# DSI_LCD.net
KiCad netlist of a schematic drawn in Altium Designer
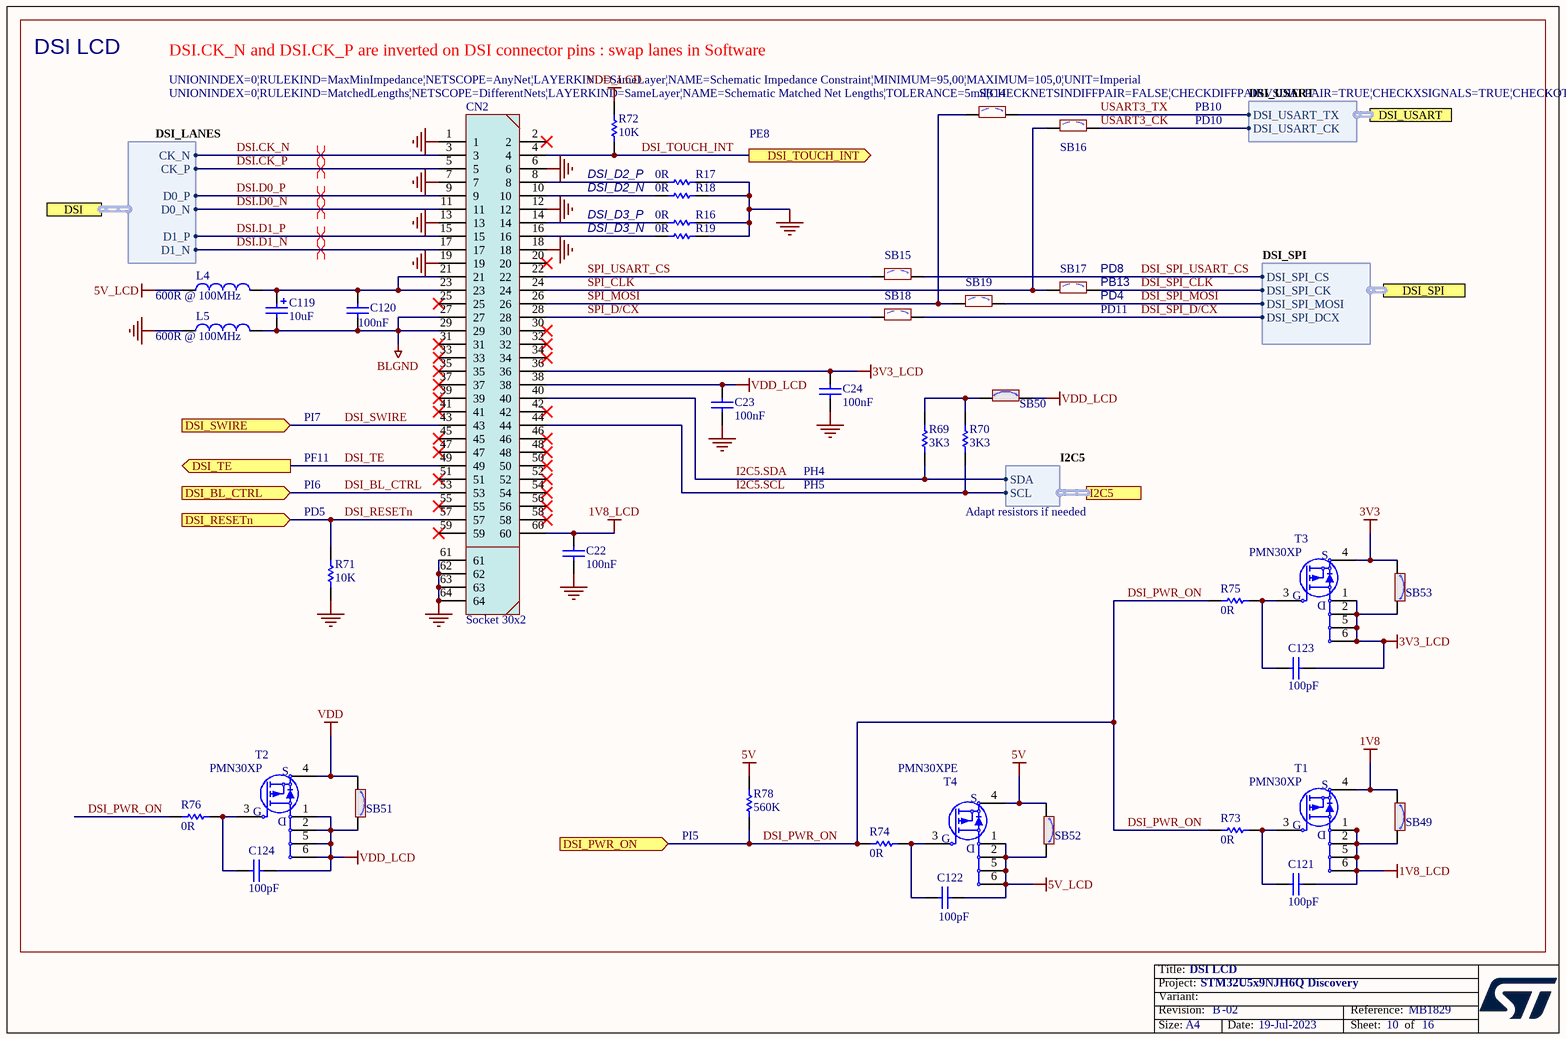
[diagram p0: DSI_LCD.SchDoc]

(export (version "E")
  (design (tool "Eeschema 10.0.6"))
  (components
    (comp (ref "C22")
      (value "100nF")
      (footprint "MCD_PARTS:C0402")
      (description "Capacitor, MLCC, 100nF, 16V, X7R, +/-10%, 0402, T=0.5mm")
      (fields
        (field (name "INTERNAL_PART_NUMBER") "MCD-00006")
        (field (name "MANUFACTURER_PART_NUMBER") "CC0402KRX7R7BB104")
      )
      (libsource (lib "MCD_PARTS_database") (part "Capacitor"))
    )
    (comp (ref "C23")
      (value "100nF")
      (footprint "MCD_PARTS:C0402")
      (description "Capacitor, MLCC, 100nF, 16V, X7R, +/-10%, 0402, T=0.5mm")
      (fields
        (field (name "INTERNAL_PART_NUMBER") "MCD-00006")
        (field (name "MANUFACTURER_PART_NUMBER") "CC0402KRX7R7BB104")
      )
      (libsource (lib "MCD_PARTS_database") (part "Capacitor"))
    )
    (comp (ref "C24")
      (value "100nF")
      (footprint "MCD_PARTS:C0402")
      (description "Capacitor, MLCC, 100nF, 16V, X7R, +/-10%, 0402, T=0.5mm")
      (fields
        (field (name "INTERNAL_PART_NUMBER") "MCD-00006")
        (field (name "MANUFACTURER_PART_NUMBER") "CC0402KRX7R7BB104")
      )
      (libsource (lib "MCD_PARTS_database") (part "Capacitor"))
    )
    (comp (ref "C119")
      (value "10uF")
      (footprint "MCD_PARTS:CPOL_TAJ-A_1206_H180")
      (description "Capacitor, Tantalum, 10uF, 16V, 3R, +/-10%, Type_A (3216 metric), T=1.6mm")
      (fields
        (field (name "INTERNAL_PART_NUMBER") "MCD-00199")
        (field (name "MANUFACTURER_PART_NUMBER") "TAJA106K016R")
      )
      (libsource (lib "MCD_PARTS_database") (part "Cap_POL_TANA"))
    )
    (comp (ref "C120")
      (value "100nF")
      (footprint "MCD_PARTS:C0402")
      (description "Capacitor, MLCC, 100nF, 16V, X7R, +/-10%, 0402, T=0.5mm")
      (fields
        (field (name "INTERNAL_PART_NUMBER") "MCD-00006")
        (field (name "MANUFACTURER_PART_NUMBER") "CC0402KRX7R7BB104")
      )
      (libsource (lib "MCD_PARTS_database") (part "Capacitor"))
    )
    (comp (ref "C121")
      (value "100pF")
      (footprint "MCD_PARTS:C0603")
      (description "Capacitor, MLCC, 100pF, 50V, X7R, +/-5%, 0603, T=0.33mm")
      (fields
        (field (name "INTERNAL_PART_NUMBER") "MCD-01101")
        (field (name "MANUFACTURER_PART_NUMBER") "06035C101JAT4A")
      )
      (libsource (lib "MCD_PARTS_database") (part "Capacitor"))
    )
    (comp (ref "C122")
      (value "100pF")
      (footprint "MCD_PARTS:C0603")
      (description "Capacitor, MLCC, 100pF, 50V, X7R, +/-5%, 0603, T=0.33mm")
      (fields
        (field (name "INTERNAL_PART_NUMBER") "MCD-01101")
        (field (name "MANUFACTURER_PART_NUMBER") "06035C101JAT4A")
      )
      (libsource (lib "MCD_PARTS_database") (part "Capacitor"))
    )
    (comp (ref "C123")
      (value "100pF")
      (footprint "MCD_PARTS:C0603")
      (description "Capacitor, MLCC, 100pF, 50V, X7R, +/-5%, 0603, T=0.33mm")
      (fields
        (field (name "INTERNAL_PART_NUMBER") "MCD-01101")
        (field (name "MANUFACTURER_PART_NUMBER") "06035C101JAT4A")
      )
      (libsource (lib "MCD_PARTS_database") (part "Capacitor"))
    )
    (comp (ref "C124")
      (value "100pF")
      (footprint "MCD_PARTS:C0603")
      (description "Capacitor, MLCC, 100pF, 50V, X7R, +/-5%, 0603, T=0.33mm")
      (fields
        (field (name "INTERNAL_PART_NUMBER") "MCD-01101")
        (field (name "MANUFACTURER_PART_NUMBER") "06035C101JAT4A")
      )
      (libsource (lib "MCD_PARTS_database") (part "Capacitor"))
    )
    (comp (ref "CN2")
      (value "Socket 30x2")
      (footprint "CON_SAMTEC_QSH-030-01-F-D-A_no-LCD-MB1835")
      (description "Socket, 30x2, 0.5mm, VR, SMD, T=3.05mm")
      (fields (field (name "INTERNAL_PART_NUMBER") "MCD-02128") (field (name "MANUFACTURER") "SAMTEC"))
      (libsource (lib "MCD_PARTS_database") (part "Socket QSH-030-01-F-D-A_DSI_LCD"))
    )
    (comp (ref "L4")
      (value "600R @ 100MHz")
      (footprint "MCD_PARTS:L0603")
      (description "Ferrite bead, 600R @1 00MHz, +/-25%, 350mA, 0R5, 0603, T=0.8mm")
      (fields
        (field (name "INTERNAL_PART_NUMBER") "MCD-00047")
        (field (name "MANUFACTURER_PART_NUMBER") "FCM1608KF-601T03")
      )
      (libsource (lib "MCD_PARTS_database") (part "BEAD"))
    )
    (comp (ref "L5")
      (value "600R @ 100MHz")
      (footprint "MCD_PARTS:L0603")
      (description "Ferrite bead, 600R @1 00MHz, +/-25%, 350mA, 0R5, 0603, T=0.8mm")
      (fields
        (field (name "INTERNAL_PART_NUMBER") "MCD-00047")
        (field (name "MANUFACTURER_PART_NUMBER") "FCM1608KF-601T03")
      )
      (libsource (lib "MCD_PARTS_database") (part "BEAD"))
    )
    (comp (ref "R16")
      (value "0R")
      (footprint "MCD_PARTS:R0402")
      (description "Resistor, 0R, 0402, +/-5%, 1/16W")
      (fields
        (field (name "INTERNAL_PART_NUMBER") "MCD-00052")
        (field (name "MANUFACTURER_PART_NUMBER") "RC0402JR-070RL")
      )
      (libsource (lib "MCD_PARTS_database") (part "Resistor"))
    )
    (comp (ref "R17")
      (value "0R")
      (footprint "MCD_PARTS:R0402")
      (description "Resistor, 0R, 0402, +/-5%, 1/16W")
      (fields
        (field (name "INTERNAL_PART_NUMBER") "MCD-00052")
        (field (name "MANUFACTURER_PART_NUMBER") "RC0402JR-070RL")
      )
      (libsource (lib "MCD_PARTS_database") (part "Resistor"))
    )
    (comp (ref "R18")
      (value "0R")
      (footprint "MCD_PARTS:R0402")
      (description "Resistor, 0R, 0402, +/-5%, 1/16W")
      (fields
        (field (name "INTERNAL_PART_NUMBER") "MCD-00052")
        (field (name "MANUFACTURER_PART_NUMBER") "RC0402JR-070RL")
      )
      (libsource (lib "MCD_PARTS_database") (part "Resistor"))
    )
    (comp (ref "R19")
      (value "0R")
      (footprint "MCD_PARTS:R0402")
      (description "Resistor, 0R, 0402, +/-5%, 1/16W")
      (fields
        (field (name "INTERNAL_PART_NUMBER") "MCD-00052")
        (field (name "MANUFACTURER_PART_NUMBER") "RC0402JR-070RL")
      )
      (libsource (lib "MCD_PARTS_database") (part "Resistor"))
    )
    (comp (ref "R69")
      (value "3K3")
      (footprint "MCD_PARTS:R0402")
      (description "Resistor, 3K3, 0402, +/-1%, 1/16W")
      (fields (field (name "INTERNAL_PART_NUMBER") "MCD-00184") (field (name "BMS_PART_NUMBER") "9131946"))
      (libsource (lib "MCD_PARTS_database") (part "Resistor"))
    )
    (comp (ref "R70")
      (value "3K3")
      (footprint "MCD_PARTS:R0402")
      (description "Resistor, 3K3, 0402, +/-1%, 1/16W")
      (fields (field (name "INTERNAL_PART_NUMBER") "MCD-00184") (field (name "BMS_PART_NUMBER") "9131946"))
      (libsource (lib "MCD_PARTS_database") (part "Resistor"))
    )
    (comp (ref "R71")
      (value "10K")
      (footprint "MCD_PARTS:R0402")
      (description "Resistor, 10K, 0402, +/-1%, 1/16W")
      (fields
        (field (name "INTERNAL_PART_NUMBER") "MCD-00053")
        (field (name "MANUFACTURER_PART_NUMBER") "RC0402FR-0710KL")
      )
      (libsource (lib "MCD_PARTS_database") (part "Resistor"))
    )
    (comp (ref "R72")
      (value "10K")
      (footprint "MCD_PARTS:R0402")
      (description "Resistor, 10K, 0402, +/-1%, 1/16W")
      (fields
        (field (name "INTERNAL_PART_NUMBER") "MCD-00053")
        (field (name "MANUFACTURER_PART_NUMBER") "RC0402FR-0710KL")
      )
      (libsource (lib "MCD_PARTS_database") (part "Resistor"))
    )
    (comp (ref "R73")
      (value "0R")
      (footprint "MCD_PARTS:R0603")
      (description "Resistor, 0R, 0603, +/-5%, 1/10W")
      (fields
        (field (name "INTERNAL_PART_NUMBER") "MCD-00056")
        (field (name "MANUFACTURER_PART_NUMBER") "RC0603JR-070RL")
      )
      (libsource (lib "MCD_PARTS_database") (part "Resistor"))
    )
    (comp (ref "R74")
      (value "0R")
      (footprint "MCD_PARTS:R0603")
      (description "Resistor, 0R, 0603, +/-5%, 1/10W")
      (fields
        (field (name "INTERNAL_PART_NUMBER") "MCD-00056")
        (field (name "MANUFACTURER_PART_NUMBER") "RC0603JR-070RL")
      )
      (libsource (lib "MCD_PARTS_database") (part "Resistor"))
    )
    (comp (ref "R75")
      (value "0R")
      (footprint "MCD_PARTS:R0603")
      (description "Resistor, 0R, 0603, +/-5%, 1/10W")
      (fields
        (field (name "INTERNAL_PART_NUMBER") "MCD-00056")
        (field (name "MANUFACTURER_PART_NUMBER") "RC0603JR-070RL")
      )
      (libsource (lib "MCD_PARTS_database") (part "Resistor"))
    )
    (comp (ref "R76")
      (value "0R")
      (footprint "MCD_PARTS:R0603")
      (description "Resistor, 0R, 0603, +/-5%, 1/10W")
      (fields
        (field (name "INTERNAL_PART_NUMBER") "MCD-00056")
        (field (name "MANUFACTURER_PART_NUMBER") "RC0603JR-070RL")
      )
      (libsource (lib "MCD_PARTS_database") (part "Resistor"))
    )
    (comp (ref "R78")
      (value "560K")
      (footprint "MCD_PARTS:R0402")
      (description "Resistor, 560K, 0402, +/-1%, 1/16W")
      (fields
        (field (name "INTERNAL_PART_NUMBER") "MCD-00495")
        (field (name "MANUFACTURER_PART_NUMBER") "RC0402FR-07560KL")
      )
      (libsource (lib "MCD_PARTS_database") (part "Resistor"))
    )
    (comp (ref "SB14")
      (value "SB_OFF")
      (footprint "MCD_PARTS:SOLDER-BRIDGE_R0402-0R")
      (description "Solder Bridge 0402 OFF")
      (fields
        (field (name "INTERNAL_PART_NUMBER") "MCD-02162")
        (field (name "MANUFACTURER_PART_NUMBER") "RC0402JR-070RL")
      )
      (libsource (lib "MCD_PARTS_database") (part "SB_OFF"))
    )
    (comp (ref "SB15")
      (value "SB_OFF")
      (footprint "MCD_PARTS:SOLDER-BRIDGE_R0402-0R")
      (description "Solder Bridge 0402 OFF")
      (fields
        (field (name "INTERNAL_PART_NUMBER") "MCD-02162")
        (field (name "MANUFACTURER_PART_NUMBER") "RC0402JR-070RL")
      )
      (libsource (lib "MCD_PARTS_database") (part "SB_OFF"))
    )
    (comp (ref "SB16")
      (value "SB_OFF")
      (footprint "MCD_PARTS:SOLDER-BRIDGE_R0402-0R")
      (description "Solder Bridge 0402 OFF")
      (fields
        (field (name "INTERNAL_PART_NUMBER") "MCD-02162")
        (field (name "MANUFACTURER_PART_NUMBER") "RC0402JR-070RL")
      )
      (libsource (lib "MCD_PARTS_database") (part "SB_OFF"))
    )
    (comp (ref "SB17")
      (value "SB_OFF")
      (footprint "MCD_PARTS:SOLDER-BRIDGE_R0402-0R")
      (description "Solder Bridge 0402 OFF")
      (fields
        (field (name "INTERNAL_PART_NUMBER") "MCD-02162")
        (field (name "MANUFACTURER_PART_NUMBER") "RC0402JR-070RL")
      )
      (libsource (lib "MCD_PARTS_database") (part "SB_OFF"))
    )
    (comp (ref "SB18")
      (value "SB_OFF")
      (footprint "MCD_PARTS:SOLDER-BRIDGE_R0402-0R")
      (description "Solder Bridge 0402 OFF")
      (fields
        (field (name "INTERNAL_PART_NUMBER") "MCD-02162")
        (field (name "MANUFACTURER_PART_NUMBER") "RC0402JR-070RL")
      )
      (libsource (lib "MCD_PARTS_database") (part "SB_OFF"))
    )
    (comp (ref "SB19")
      (value "SB_OFF")
      (footprint "MCD_PARTS:SOLDER-BRIDGE_R0402-0R")
      (description "Solder Bridge 0402 OFF")
      (fields
        (field (name "INTERNAL_PART_NUMBER") "MCD-02162")
        (field (name "MANUFACTURER_PART_NUMBER") "RC0402JR-070RL")
      )
      (libsource (lib "MCD_PARTS_database") (part "SB_OFF"))
    )
    (comp (ref "SB49")
      (value "SB_ON")
      (footprint "MCD_PARTS:SOLDER-BRIDGE_R0402-0R")
      (description "Solder Bridge 0402 ON")
      (fields
        (field (name "INTERNAL_PART_NUMBER") "MCD-01618")
        (field (name "MANUFACTURER_PART_NUMBER") "RC0402JR-070RL")
      )
      (libsource (lib "MCD_PARTS_database") (part "SB_ON"))
    )
    (comp (ref "SB50")
      (value "SB_ON")
      (footprint "MCD_PARTS:SOLDER-BRIDGE_R0402-0R")
      (description "Solder Bridge 0402 ON")
      (fields
        (field (name "INTERNAL_PART_NUMBER") "MCD-01618")
        (field (name "MANUFACTURER_PART_NUMBER") "RC0402JR-070RL")
      )
      (libsource (lib "") (part "SB_ON_1"))
    )
    (comp (ref "SB51")
      (value "SB_ON")
      (footprint "MCD_PARTS:SOLDER-BRIDGE_R0402-0R")
      (description "Solder Bridge 0402 ON")
      (fields
        (field (name "INTERNAL_PART_NUMBER") "MCD-01618")
        (field (name "MANUFACTURER_PART_NUMBER") "RC0402JR-070RL")
      )
      (libsource (lib "MCD_PARTS_database") (part "SB_ON"))
    )
    (comp (ref "SB52")
      (value "SB_ON")
      (footprint "MCD_PARTS:SOLDER-BRIDGE_R0402-0R")
      (description "Solder Bridge 0402 ON")
      (fields
        (field (name "INTERNAL_PART_NUMBER") "MCD-01618")
        (field (name "MANUFACTURER_PART_NUMBER") "RC0402JR-070RL")
      )
      (libsource (lib "MCD_PARTS_database") (part "SB_ON"))
    )
    (comp (ref "SB53")
      (value "SB_ON")
      (footprint "MCD_PARTS:SOLDER-BRIDGE_R0402-0R")
      (description "Solder Bridge 0402 ON")
      (fields
        (field (name "INTERNAL_PART_NUMBER") "MCD-01618")
        (field (name "MANUFACTURER_PART_NUMBER") "RC0402JR-070RL")
      )
      (libsource (lib "MCD_PARTS_database") (part "SB_ON"))
    )
    (comp (ref "T1")
      (value "PMN30XP")
      (footprint "MCD_PARTS:MOS_SOT23-6L")
      (description "20 V, P-channel Trench MOSFET")
      (fields
        (field (name "INTERNAL_PART_NUMBER") "MCD-01926")
        (field (name "MANUFACTURER_PART_NUMBER") "PMN30XPX")
      )
      (libsource (lib "MCD_PARTS_database") (part "PMN30XP"))
    )
    (comp (ref "T2")
      (value "PMN30XP")
      (footprint "MCD_PARTS:MOS_SOT23-6L")
      (description "20 V, P-channel Trench MOSFET")
      (fields
        (field (name "INTERNAL_PART_NUMBER") "MCD-01926")
        (field (name "MANUFACTURER_PART_NUMBER") "PMN30XPX")
      )
      (libsource (lib "MCD_PARTS_database") (part "PMN30XP"))
    )
    (comp (ref "T3")
      (value "PMN30XP")
      (footprint "MCD_PARTS:MOS_SOT23-6L")
      (description "20 V, P-channel Trench MOSFET")
      (fields
        (field (name "INTERNAL_PART_NUMBER") "MCD-01926")
        (field (name "MANUFACTURER_PART_NUMBER") "PMN30XPX")
      )
      (libsource (lib "MCD_PARTS_database") (part "PMN30XP"))
    )
    (comp (ref "T4")
      (value "PMN30XPE")
      (footprint "MOS_SOT23-6L")
      (description "Transistor, MOSFET, P-CH, -20V, 7A, SOT457")
      (fields (field (name "INTERNAL_PART_NUMBER") "MCD-03170") (field (name "MANUFACTURER") "NEXPERIA"))
      (libsource (lib "MCD_PARTS_database") (part "PMN30XP"))
    )
  )
  (nets
    (net (code "6") (name "/DSI.CK_N") (class "Default")
      (node (ref "CN2") (pin "3") (pinfunction "3_3") (pintype "passive"))
    )
    (net (code "7") (name "/DSI.CK_P") (class "Default")
      (node (ref "CN2") (pin "5") (pinfunction "5_5") (pintype "passive"))
    )
    (net (code "8") (name "/DSI.D0_N") (class "Default")
      (node (ref "CN2") (pin "11") (pinfunction "11_11") (pintype "passive"))
    )
    (net (code "9") (name "/DSI.D0_P") (class "Default")
      (node (ref "CN2") (pin "9") (pinfunction "9_9") (pintype "passive"))
    )
    (net (code "10") (name "/DSI.D1_N") (class "Default")
      (node (ref "CN2") (pin "17") (pinfunction "17_17") (pintype "passive"))
    )
    (net (code "11") (name "/DSI.D1_P") (class "Default")
      (node (ref "CN2") (pin "15") (pinfunction "15_15") (pintype "passive"))
    )
    (net (code "12") (name "/DSI_BL_CTRL") (class "Default")
      (node (ref "CN2") (pin "53") (pinfunction "53_53") (pintype "passive"))
    )
    (net (code "13") (name "/DSI_PWR_ON") (class "Default")
      (node (ref "R73") (pin "1") (pinfunction "1_1") (pintype "passive"))
      (node (ref "R74") (pin "1") (pinfunction "1_1") (pintype "passive"))
      (node (ref "R75") (pin "1") (pinfunction "1_1") (pintype "passive"))
      (node (ref "R76") (pin "1") (pinfunction "1_1") (pintype "passive"))
      (node (ref "R78") (pin "1") (pinfunction "1_1") (pintype "passive"))
    )
    (net (code "14") (name "/DSI_RESETn") (class "Default")
      (node (ref "CN2") (pin "57") (pinfunction "57_57") (pintype "passive"))
      (node (ref "R71") (pin "2") (pinfunction "2_2") (pintype "passive"))
    )
    (net (code "15") (name "/DSI_SPI_CLK") (class "Default")
      (node (ref "SB17") (pin "2") (pinfunction "2_2") (pintype "passive"))
    )
    (net (code "16") (name "/DSI_SPI_D{slash}CX") (class "Default")
      (node (ref "SB18") (pin "2") (pinfunction "2_2") (pintype "passive"))
    )
    (net (code "17") (name "/DSI_SPI_MOSI") (class "Default")
      (node (ref "SB19") (pin "2") (pinfunction "2_2") (pintype "passive"))
    )
    (net (code "18") (name "/DSI_SPI_USART_CS") (class "Default")
      (node (ref "SB15") (pin "2") (pinfunction "2_2") (pintype "passive"))
    )
    (net (code "19") (name "/DSI_SWIRE") (class "Default")
      (node (ref "CN2") (pin "43") (pinfunction "43_43") (pintype "passive"))
    )
    (net (code "20") (name "/DSI_TE") (class "Default")
      (node (ref "CN2") (pin "49") (pinfunction "49_49") (pintype "passive"))
    )
    (net (code "21") (name "/DSI_TOUCH_INT") (class "Default")
      (node (ref "CN2") (pin "4") (pinfunction "4_4") (pintype "passive"))
      (node (ref "R72") (pin "1") (pinfunction "1_1") (pintype "passive"))
    )
    (net (code "22") (name "/I2C5.SCL") (class "Default")
      (node (ref "CN2") (pin "44") (pinfunction "44_44") (pintype "passive"))
      (node (ref "R70") (pin "2") (pinfunction "2_2") (pintype "passive"))
    )
    (net (code "23") (name "/I2C5.SDA") (class "Default")
      (node (ref "CN2") (pin "40") (pinfunction "40_40") (pintype "passive"))
      (node (ref "R69") (pin "2") (pinfunction "2_2") (pintype "passive"))
    )
    (net (code "24") (name "/SPI_CLK") (class "Default")
      (node (ref "CN2") (pin "24") (pinfunction "24_24") (pintype "passive"))
      (node (ref "SB16") (pin "1") (pinfunction "1_1") (pintype "passive"))
      (node (ref "SB17") (pin "1") (pinfunction "1_1") (pintype "passive"))
    )
    (net (code "25") (name "/SPI_D{slash}CX") (class "Default")
      (node (ref "CN2") (pin "28") (pinfunction "28_28") (pintype "passive"))
      (node (ref "SB18") (pin "1") (pinfunction "1_1") (pintype "passive"))
    )
    (net (code "26") (name "/SPI_MOSI") (class "Default")
      (node (ref "CN2") (pin "26") (pinfunction "26_26") (pintype "passive"))
      (node (ref "SB14") (pin "1") (pinfunction "1_1") (pintype "passive"))
      (node (ref "SB19") (pin "1") (pinfunction "1_1") (pintype "passive"))
    )
    (net (code "27") (name "/SPI_USART_CS") (class "Default")
      (node (ref "CN2") (pin "22") (pinfunction "22_22") (pintype "passive"))
      (node (ref "SB15") (pin "1") (pinfunction "1_1") (pintype "passive"))
    )
    (net (code "28") (name "/USART3_CK") (class "Default")
      (node (ref "SB16") (pin "2") (pinfunction "2_2") (pintype "passive"))
    )
    (net (code "29") (name "/USART3_TX") (class "Default")
      (node (ref "SB14") (pin "2") (pinfunction "2_2") (pintype "passive"))
    )
    (net (code "34") (name "1V8") (class "Default")
      (node (ref "SB49") (pin "1") (pinfunction "1_1") (pintype "passive"))
      (node (ref "T1") (pin "4") (pinfunction "S_4") (pintype "passive"))
    )
    (net (code "35") (name "1V8_LCD") (class "Default")
      (node (ref "C121") (pin "2") (pinfunction "2_2") (pintype "passive"))
      (node (ref "C22") (pin "2") (pinfunction "2_2") (pintype "passive"))
      (node (ref "CN2") (pin "60") (pinfunction "60_60") (pintype "passive"))
      (node (ref "SB49") (pin "2") (pinfunction "2_2") (pintype "passive"))
      (node (ref "T1") (pin "1") (pinfunction "S_1") (pintype "passive"))
      (node (ref "T1") (pin "2") (pinfunction "S_2") (pintype "passive"))
      (node (ref "T1") (pin "5") (pinfunction "D_5") (pintype "passive"))
      (node (ref "T1") (pin "6") (pinfunction "D_6") (pintype "passive"))
    )
    (net (code "36") (name "3V3") (class "Default")
      (node (ref "SB53") (pin "1") (pinfunction "1_1") (pintype "passive"))
      (node (ref "T3") (pin "4") (pinfunction "S_4") (pintype "passive"))
    )
    (net (code "37") (name "3V3_LCD") (class "Default")
      (node (ref "C123") (pin "2") (pinfunction "2_2") (pintype "passive"))
      (node (ref "C24") (pin "2") (pinfunction "2_2") (pintype "passive"))
      (node (ref "CN2") (pin "36") (pinfunction "36_36") (pintype "passive"))
      (node (ref "SB53") (pin "2") (pinfunction "2_2") (pintype "passive"))
      (node (ref "T3") (pin "1") (pinfunction "S_1") (pintype "passive"))
      (node (ref "T3") (pin "2") (pinfunction "S_2") (pintype "passive"))
      (node (ref "T3") (pin "5") (pinfunction "D_5") (pintype "passive"))
      (node (ref "T3") (pin "6") (pinfunction "D_6") (pintype "passive"))
    )
    (net (code "38") (name "5V") (class "Default")
      (node (ref "R78") (pin "2") (pinfunction "2_2") (pintype "passive"))
      (node (ref "SB52") (pin "1") (pinfunction "1_1") (pintype "passive"))
      (node (ref "T4") (pin "4") (pinfunction "S_4") (pintype "passive"))
    )
    (net (code "39") (name "5V_LCD") (class "Default")
      (node (ref "C122") (pin "2") (pinfunction "2_2") (pintype "passive"))
      (node (ref "L4") (pin "1") (pinfunction "1_1") (pintype "passive"))
      (node (ref "SB52") (pin "2") (pinfunction "2_2") (pintype "passive"))
      (node (ref "T4") (pin "1") (pinfunction "S_1") (pintype "passive"))
      (node (ref "T4") (pin "2") (pinfunction "S_2") (pintype "passive"))
      (node (ref "T4") (pin "5") (pinfunction "D_5") (pintype "passive"))
      (node (ref "T4") (pin "6") (pinfunction "D_6") (pintype "passive"))
    )
    (net (code "40") (name "BLGND") (class "Default")
      (node (ref "C119") (pin "2") (pinfunction "2_2") (pintype "passive"))
      (node (ref "C120") (pin "1") (pinfunction "1_1") (pintype "passive"))
      (node (ref "CN2") (pin "27") (pinfunction "27_27") (pintype "passive"))
      (node (ref "CN2") (pin "29") (pinfunction "29_29") (pintype "passive"))
      (node (ref "L5") (pin "2") (pinfunction "2_2") (pintype "passive"))
    )
    (net (code "41") (name "GND") (class "Default")
      (node (ref "C22") (pin "1") (pinfunction "1_1") (pintype "passive"))
      (node (ref "C23") (pin "1") (pinfunction "1_1") (pintype "passive"))
      (node (ref "C24") (pin "1") (pinfunction "1_1") (pintype "passive"))
      (node (ref "CN2") (pin "1") (pinfunction "1_1") (pintype "passive"))
      (node (ref "CN2") (pin "12") (pinfunction "12_12") (pintype "passive"))
      (node (ref "CN2") (pin "13") (pinfunction "13_13") (pintype "passive"))
      (node (ref "CN2") (pin "18") (pinfunction "18_18") (pintype "passive"))
      (node (ref "CN2") (pin "19") (pinfunction "19_19") (pintype "passive"))
      (node (ref "CN2") (pin "6") (pinfunction "6_6") (pintype "passive"))
      (node (ref "CN2") (pin "61") (pinfunction "61_61") (pintype "passive"))
      (node (ref "CN2") (pin "62") (pinfunction "62_62") (pintype "passive"))
      (node (ref "CN2") (pin "63") (pinfunction "63_63") (pintype "passive"))
      (node (ref "CN2") (pin "64") (pinfunction "64_64") (pintype "passive"))
      (node (ref "CN2") (pin "7") (pinfunction "7_7") (pintype "passive"))
      (node (ref "L5") (pin "1") (pinfunction "1_1") (pintype "passive"))
      (node (ref "R16") (pin "2") (pinfunction "2_2") (pintype "passive"))
      (node (ref "R17") (pin "2") (pinfunction "2_2") (pintype "passive"))
      (node (ref "R18") (pin "2") (pinfunction "2_2") (pintype "passive"))
      (node (ref "R19") (pin "2") (pinfunction "2_2") (pintype "passive"))
      (node (ref "R71") (pin "1") (pinfunction "1_1") (pintype "passive"))
    )
    (net (code "42") (name "Net-(C119-Pad1)") (class "Default")
      (node (ref "C119") (pin "1") (pinfunction "1_1") (pintype "passive"))
      (node (ref "C120") (pin "2") (pinfunction "2_2") (pintype "passive"))
      (node (ref "CN2") (pin "21") (pinfunction "21_21") (pintype "passive"))
      (node (ref "CN2") (pin "23") (pinfunction "23_23") (pintype "passive"))
      (node (ref "L4") (pin "2") (pinfunction "2_2") (pintype "passive"))
    )
    (net (code "43") (name "Net-(CN2-Pad8)") (class "Default")
      (node (ref "CN2") (pin "8") (pinfunction "8_8") (pintype "passive"))
      (node (ref "R17") (pin "1") (pinfunction "1_1") (pintype "passive"))
    )
    (net (code "44") (name "Net-(CN2-Pad10)") (class "Default")
      (node (ref "CN2") (pin "10") (pinfunction "10_10") (pintype "passive"))
      (node (ref "R18") (pin "1") (pinfunction "1_1") (pintype "passive"))
    )
    (net (code "45") (name "Net-(CN2-Pad14)") (class "Default")
      (node (ref "CN2") (pin "14") (pinfunction "14_14") (pintype "passive"))
      (node (ref "R16") (pin "1") (pinfunction "1_1") (pintype "passive"))
    )
    (net (code "46") (name "Net-(CN2-Pad16)") (class "Default")
      (node (ref "CN2") (pin "16") (pinfunction "16_16") (pintype "passive"))
      (node (ref "R19") (pin "1") (pinfunction "1_1") (pintype "passive"))
    )
    (net (code "47") (name "Net-(R69-Pad1)") (class "Default")
      (node (ref "R69") (pin "1") (pinfunction "1_1") (pintype "passive"))
      (node (ref "R70") (pin "1") (pinfunction "1_1") (pintype "passive"))
      (node (ref "SB50") (pin "1") (pinfunction "1_1") (pintype "passive"))
    )
    (net (code "48") (name "Net-(T1-G)") (class "Default")
      (node (ref "C121") (pin "1") (pinfunction "1_1") (pintype "passive"))
      (node (ref "R73") (pin "2") (pinfunction "2_2") (pintype "passive"))
      (node (ref "T1") (pin "3") (pinfunction "G_3") (pintype "passive"))
    )
    (net (code "49") (name "Net-(T2-G)") (class "Default")
      (node (ref "C124") (pin "1") (pinfunction "1_1") (pintype "passive"))
      (node (ref "R76") (pin "2") (pinfunction "2_2") (pintype "passive"))
      (node (ref "T2") (pin "3") (pinfunction "G_3") (pintype "passive"))
    )
    (net (code "50") (name "Net-(T3-G)") (class "Default")
      (node (ref "C123") (pin "1") (pinfunction "1_1") (pintype "passive"))
      (node (ref "R75") (pin "2") (pinfunction "2_2") (pintype "passive"))
      (node (ref "T3") (pin "3") (pinfunction "G_3") (pintype "passive"))
    )
    (net (code "51") (name "Net-(T4-G)") (class "Default")
      (node (ref "C122") (pin "1") (pinfunction "1_1") (pintype "passive"))
      (node (ref "R74") (pin "2") (pinfunction "2_2") (pintype "passive"))
      (node (ref "T4") (pin "3") (pinfunction "G_3") (pintype "passive"))
    )
    (net (code "52") (name "VDD") (class "Default")
      (node (ref "SB51") (pin "1") (pinfunction "1_1") (pintype "passive"))
      (node (ref "T2") (pin "4") (pinfunction "S_4") (pintype "passive"))
    )
    (net (code "53") (name "VDD_LCD") (class "Default")
      (node (ref "C124") (pin "2") (pinfunction "2_2") (pintype "passive"))
      (node (ref "C23") (pin "2") (pinfunction "2_2") (pintype "passive"))
      (node (ref "CN2") (pin "38") (pinfunction "38_38") (pintype "passive"))
      (node (ref "R72") (pin "2") (pinfunction "2_2") (pintype "passive"))
      (node (ref "SB50") (pin "2") (pinfunction "2_2") (pintype "passive"))
      (node (ref "SB51") (pin "2") (pinfunction "2_2") (pintype "passive"))
      (node (ref "T2") (pin "1") (pinfunction "S_1") (pintype "passive"))
      (node (ref "T2") (pin "2") (pinfunction "S_2") (pintype "passive"))
      (node (ref "T2") (pin "5") (pinfunction "D_5") (pintype "passive"))
      (node (ref "T2") (pin "6") (pinfunction "D_6") (pintype "passive"))
    )
    (net (code "54") (name "unconnected-(CN2-Pad2)") (class "Default")
      (node (ref "CN2") (pin "2") (pinfunction "2_2") (pintype "passive+no_connect"))
    )
    (net (code "55") (name "unconnected-(CN2-Pad20)") (class "Default")
      (node (ref "CN2") (pin "20") (pinfunction "20_20") (pintype "passive+no_connect"))
    )
    (net (code "56") (name "unconnected-(CN2-Pad25)") (class "Default")
      (node (ref "CN2") (pin "25") (pinfunction "25_25") (pintype "passive+no_connect"))
    )
    (net (code "57") (name "unconnected-(CN2-Pad30)") (class "Default")
      (node (ref "CN2") (pin "30") (pinfunction "30_30") (pintype "passive+no_connect"))
    )
    (net (code "58") (name "unconnected-(CN2-Pad31)") (class "Default")
      (node (ref "CN2") (pin "31") (pinfunction "31_31") (pintype "passive+no_connect"))
    )
    (net (code "59") (name "unconnected-(CN2-Pad32)") (class "Default")
      (node (ref "CN2") (pin "32") (pinfunction "32_32") (pintype "passive+no_connect"))
    )
    (net (code "60") (name "unconnected-(CN2-Pad33)") (class "Default")
      (node (ref "CN2") (pin "33") (pinfunction "33_33") (pintype "passive+no_connect"))
    )
    (net (code "61") (name "unconnected-(CN2-Pad34)") (class "Default")
      (node (ref "CN2") (pin "34") (pinfunction "34_34") (pintype "passive+no_connect"))
    )
    (net (code "62") (name "unconnected-(CN2-Pad35)") (class "Default")
      (node (ref "CN2") (pin "35") (pinfunction "35_35") (pintype "passive+no_connect"))
    )
    (net (code "63") (name "unconnected-(CN2-Pad37)") (class "Default")
      (node (ref "CN2") (pin "37") (pinfunction "37_37") (pintype "passive+no_connect"))
    )
    (net (code "64") (name "unconnected-(CN2-Pad39)") (class "Default")
      (node (ref "CN2") (pin "39") (pinfunction "39_39") (pintype "passive+no_connect"))
    )
    (net (code "65") (name "unconnected-(CN2-Pad41)") (class "Default")
      (node (ref "CN2") (pin "41") (pinfunction "41_41") (pintype "passive+no_connect"))
    )
    (net (code "66") (name "unconnected-(CN2-Pad42)") (class "Default")
      (node (ref "CN2") (pin "42") (pinfunction "42_42") (pintype "passive+no_connect"))
    )
    (net (code "67") (name "unconnected-(CN2-Pad45)") (class "Default")
      (node (ref "CN2") (pin "45") (pinfunction "45_45") (pintype "passive+no_connect"))
    )
    (net (code "68") (name "unconnected-(CN2-Pad46)") (class "Default")
      (node (ref "CN2") (pin "46") (pinfunction "46_46") (pintype "passive+no_connect"))
    )
    (net (code "69") (name "unconnected-(CN2-Pad47)") (class "Default")
      (node (ref "CN2") (pin "47") (pinfunction "47_47") (pintype "passive+no_connect"))
    )
    (net (code "70") (name "unconnected-(CN2-Pad48)") (class "Default")
      (node (ref "CN2") (pin "48") (pinfunction "48_48") (pintype "passive+no_connect"))
    )
    (net (code "71") (name "unconnected-(CN2-Pad50)") (class "Default")
      (node (ref "CN2") (pin "50") (pinfunction "50_50") (pintype "passive+no_connect"))
    )
    (net (code "72") (name "unconnected-(CN2-Pad51)") (class "Default")
      (node (ref "CN2") (pin "51") (pinfunction "51_51") (pintype "passive+no_connect"))
    )
    (net (code "73") (name "unconnected-(CN2-Pad52)") (class "Default")
      (node (ref "CN2") (pin "52") (pinfunction "52_52") (pintype "passive+no_connect"))
    )
    (net (code "74") (name "unconnected-(CN2-Pad54)") (class "Default")
      (node (ref "CN2") (pin "54") (pinfunction "54_54") (pintype "passive+no_connect"))
    )
    (net (code "75") (name "unconnected-(CN2-Pad55)") (class "Default")
      (node (ref "CN2") (pin "55") (pinfunction "55_55") (pintype "passive+no_connect"))
    )
    (net (code "76") (name "unconnected-(CN2-Pad56)") (class "Default")
      (node (ref "CN2") (pin "56") (pinfunction "56_56") (pintype "passive+no_connect"))
    )
    (net (code "77") (name "unconnected-(CN2-Pad58)") (class "Default")
      (node (ref "CN2") (pin "58") (pinfunction "58_58") (pintype "passive+no_connect"))
    )
    (net (code "78") (name "unconnected-(CN2-Pad59)") (class "Default")
      (node (ref "CN2") (pin "59") (pinfunction "59_59") (pintype "passive+no_connect"))
    )
  )
)
